# Thermocouple_datalogger_RevB.net
KiCad netlist of a schematic drawn in EAGLE
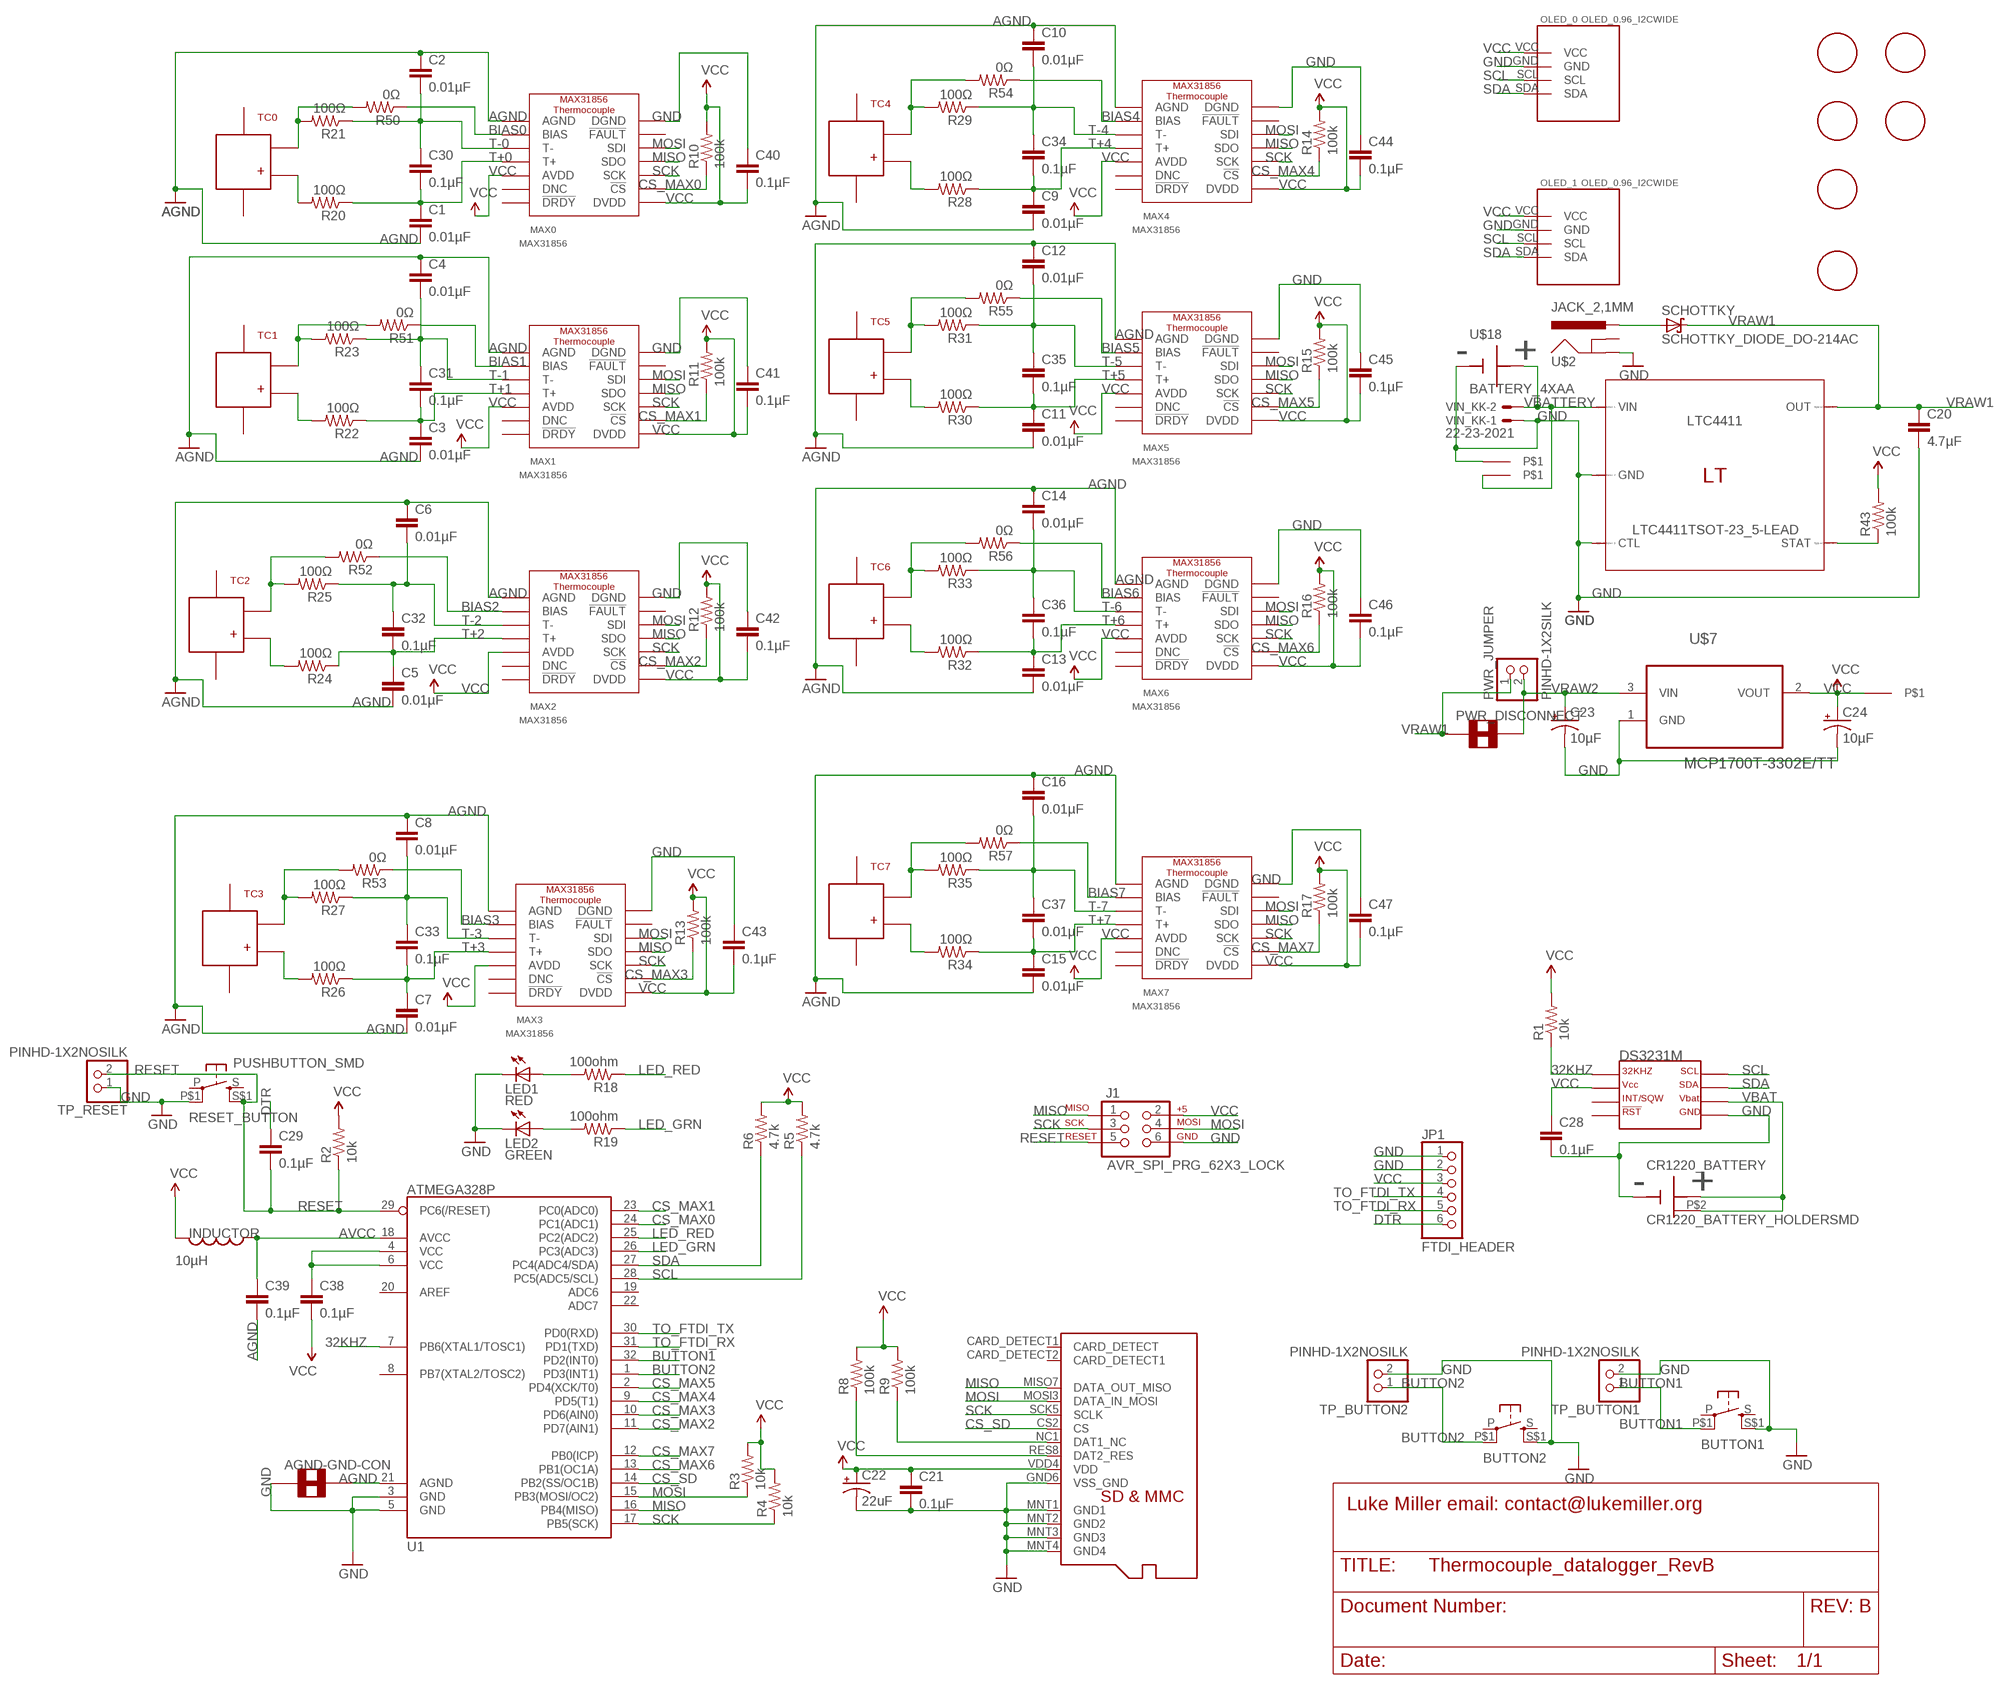
[diagram p0: schematic, sheet 1]

(export (version "E")
  (design (tool "Eeschema 10.0.6"))
  (components
    (comp (ref "AGND-GND-CON")
      (value "SOLDER_JUMPER_TRACESTANDARD")
      (footprint "eagle-import:SJ_2S-TRACE")
      (libsource (lib "eagle-import") (part "SOLDER_JUMPER_TRACESTANDARD"))
    )
    (comp (ref "BUTTON1")
      (value "PUSHBUTTON_DPST_SMDSTANDARD")
      (footprint "eagle-import:PUSHBUTTON_DPST_SMD")
      (libsource (lib "eagle-import") (part "PUSHBUTTON_DPST_SMDSTANDARD"))
    )
    (comp (ref "BUTTON2")
      (value "PUSHBUTTON_DPST_SMDSTANDARD")
      (footprint "eagle-import:PUSHBUTTON_DPST_SMD")
      (libsource (lib "eagle-import") (part "PUSHBUTTON_DPST_SMDSTANDARD"))
    )
    (comp (ref "C1")
      (value "0.01µF")
      (footprint "eagle-import:0805")
      (libsource (lib "eagle-import") (part "CAP0805"))
    )
    (comp (ref "C2")
      (value "0.01µF")
      (footprint "eagle-import:0805")
      (libsource (lib "eagle-import") (part "CAP0805"))
    )
    (comp (ref "C3")
      (value "0.01µF")
      (footprint "eagle-import:0805")
      (libsource (lib "eagle-import") (part "CAP0805"))
    )
    (comp (ref "C4")
      (value "0.01µF")
      (footprint "eagle-import:0805")
      (libsource (lib "eagle-import") (part "CAP0805"))
    )
    (comp (ref "C5")
      (value "0.01µF")
      (footprint "eagle-import:0805")
      (libsource (lib "eagle-import") (part "CAP0805"))
    )
    (comp (ref "C6")
      (value "0.01µF")
      (footprint "eagle-import:0805")
      (libsource (lib "eagle-import") (part "CAP0805"))
    )
    (comp (ref "C7")
      (value "0.01µF")
      (footprint "eagle-import:0805")
      (libsource (lib "eagle-import") (part "CAP0805"))
    )
    (comp (ref "C8")
      (value "0.01µF")
      (footprint "eagle-import:0805")
      (libsource (lib "eagle-import") (part "CAP0805"))
    )
    (comp (ref "C9")
      (value "0.01µF")
      (footprint "eagle-import:0805")
      (libsource (lib "eagle-import") (part "CAP0805"))
    )
    (comp (ref "C10")
      (value "0.01µF")
      (footprint "eagle-import:0805")
      (libsource (lib "eagle-import") (part "CAP0805"))
    )
    (comp (ref "C11")
      (value "0.01µF")
      (footprint "eagle-import:0805")
      (libsource (lib "eagle-import") (part "CAP0805"))
    )
    (comp (ref "C12")
      (value "0.01µF")
      (footprint "eagle-import:0805")
      (libsource (lib "eagle-import") (part "CAP0805"))
    )
    (comp (ref "C13")
      (value "0.01µF")
      (footprint "eagle-import:0805")
      (libsource (lib "eagle-import") (part "CAP0805"))
    )
    (comp (ref "C14")
      (value "0.01µF")
      (footprint "eagle-import:0805")
      (libsource (lib "eagle-import") (part "CAP0805"))
    )
    (comp (ref "C15")
      (value "0.01µF")
      (footprint "eagle-import:0805")
      (libsource (lib "eagle-import") (part "CAP0805"))
    )
    (comp (ref "C16")
      (value "0.01µF")
      (footprint "eagle-import:0805")
      (libsource (lib "eagle-import") (part "CAP0805"))
    )
    (comp (ref "C20")
      (value "4.7µF")
      (footprint "eagle-import:0805")
      (libsource (lib "eagle-import") (part "CAP0805"))
    )
    (comp (ref "C21")
      (value "0.1µF")
      (footprint "eagle-import:0805")
      (libsource (lib "eagle-import") (part "CAP0805"))
    )
    (comp (ref "C22")
      (value "22uF")
      (footprint "eagle-import:C0805_POL")
      (libsource (lib "eagle-import") (part "CPOL-US0805"))
    )
    (comp (ref "C23")
      (value "10µF")
      (footprint "eagle-import:PANASONIC_B")
      (libsource (lib "eagle-import") (part "CPOL-USB"))
    )
    (comp (ref "C24")
      (value "10µF")
      (footprint "eagle-import:PANASONIC_B")
      (libsource (lib "eagle-import") (part "CPOL-USB"))
    )
    (comp (ref "C28")
      (value "0.1µF")
      (footprint "eagle-import:0805")
      (libsource (lib "eagle-import") (part "CAP0805"))
    )
    (comp (ref "C29")
      (value "0.1µF")
      (footprint "eagle-import:0805")
      (libsource (lib "eagle-import") (part "CAP0805"))
    )
    (comp (ref "C30")
      (value "0.1µF")
      (footprint "eagle-import:0805")
      (libsource (lib "eagle-import") (part "CAP0805"))
    )
    (comp (ref "C31")
      (value "0.1µF")
      (footprint "eagle-import:0805")
      (libsource (lib "eagle-import") (part "CAP0805"))
    )
    (comp (ref "C32")
      (value "0.1µF")
      (footprint "eagle-import:0805")
      (libsource (lib "eagle-import") (part "CAP0805"))
    )
    (comp (ref "C33")
      (value "0.1µF")
      (footprint "eagle-import:0805")
      (libsource (lib "eagle-import") (part "CAP0805"))
    )
    (comp (ref "C34")
      (value "0.1µF")
      (footprint "eagle-import:0805")
      (libsource (lib "eagle-import") (part "CAP0805"))
    )
    (comp (ref "C35")
      (value "0.1µF")
      (footprint "eagle-import:0805")
      (libsource (lib "eagle-import") (part "CAP0805"))
    )
    (comp (ref "C36")
      (value "0.1µF")
      (footprint "eagle-import:0805")
      (libsource (lib "eagle-import") (part "CAP0805"))
    )
    (comp (ref "C37")
      (value "0.01µF")
      (footprint "eagle-import:0805")
      (libsource (lib "eagle-import") (part "CAP0805"))
    )
    (comp (ref "C38")
      (value "0.1µF")
      (footprint "eagle-import:0805")
      (libsource (lib "eagle-import") (part "CAP0805"))
    )
    (comp (ref "C39")
      (value "0.1µF")
      (footprint "eagle-import:0805")
      (libsource (lib "eagle-import") (part "CAP0805"))
    )
    (comp (ref "C40")
      (value "0.1µF")
      (footprint "eagle-import:0805")
      (libsource (lib "eagle-import") (part "CAP0805"))
    )
    (comp (ref "C41")
      (value "0.1µF")
      (footprint "eagle-import:0805")
      (libsource (lib "eagle-import") (part "CAP0805"))
    )
    (comp (ref "C42")
      (value "0.1µF")
      (footprint "eagle-import:0805")
      (libsource (lib "eagle-import") (part "CAP0805"))
    )
    (comp (ref "C43")
      (value "0.1µF")
      (footprint "eagle-import:0805")
      (libsource (lib "eagle-import") (part "CAP0805"))
    )
    (comp (ref "C44")
      (value "0.1µF")
      (footprint "eagle-import:0805")
      (libsource (lib "eagle-import") (part "CAP0805"))
    )
    (comp (ref "C45")
      (value "0.1µF")
      (footprint "eagle-import:0805")
      (libsource (lib "eagle-import") (part "CAP0805"))
    )
    (comp (ref "C46")
      (value "0.1µF")
      (footprint "eagle-import:0805")
      (libsource (lib "eagle-import") (part "CAP0805"))
    )
    (comp (ref "C47")
      (value "0.1µF")
      (footprint "eagle-import:0805")
      (libsource (lib "eagle-import") (part "CAP0805"))
    )
    (comp (ref "CR1220_BATTERY")
      (value "CR1220_BATTERY_HOLDERSMD")
      (footprint "eagle-import:CR1220_BATTERY_HOLDER_SMD")
      (libsource (lib "eagle-import") (part "CR1220_BATTERY_HOLDERSMD"))
    )
    (comp (ref "DS3231M")
      (value "DS3231MSOIC-8")
      (footprint "eagle-import:DS3231M_SOIC8")
      (libsource (lib "eagle-import") (part "DS3231MSOIC-8"))
    )
    (comp (ref "INDUCTOR")
      (value "10µH")
      (footprint "eagle-import:I_0805")
      (libsource (lib "eagle-import") (part "INDUCTOR0805_TY"))
    )
    (comp (ref "J1")
      (value "AVR_SPI_PRG_62X3_LOCK")
      (footprint "eagle-import:2X3_LOCK")
      (libsource (lib "eagle-import") (part "AVR_SPI_PRG_62X3_LOCK"))
    )
    (comp (ref "JP1")
      (value "FTDI_HEADER")
      (footprint "eagle-import:1X06-RIGHT_ANGLE")
      (libsource (lib "eagle-import") (part "PINHD-1X6RA"))
    )
    (comp (ref "LED1")
      (value "RED")
      (footprint "eagle-import:CHIPLED_0805")
      (libsource (lib "eagle-import") (part "LED0805"))
    )
    (comp (ref "LED2")
      (value "GREEN")
      (footprint "eagle-import:CHIPLED_0805")
      (libsource (lib "eagle-import") (part "LED0805"))
    )
    (comp (ref "LTC4411")
      (value "LTC4411TSOT-23_5-LEAD")
      (footprint "eagle-import:TSOT-23_5-LEAD")
      (libsource (lib "eagle-import") (part "LTC4411TSOT-23_5-LEAD"))
    )
    (comp (ref "MAX0")
      (value "MAX31856")
      (footprint "eagle-import:MAX31856_TSSOP14")
      (libsource (lib "eagle-import") (part "MAX31856"))
    )
    (comp (ref "MAX1")
      (value "MAX31856")
      (footprint "eagle-import:MAX31856_TSSOP14")
      (libsource (lib "eagle-import") (part "MAX31856"))
    )
    (comp (ref "MAX2")
      (value "MAX31856")
      (footprint "eagle-import:MAX31856_TSSOP14")
      (libsource (lib "eagle-import") (part "MAX31856"))
    )
    (comp (ref "MAX3")
      (value "MAX31856")
      (footprint "eagle-import:MAX31856_TSSOP14")
      (libsource (lib "eagle-import") (part "MAX31856"))
    )
    (comp (ref "MAX4")
      (value "MAX31856")
      (footprint "eagle-import:MAX31856_TSSOP14")
      (libsource (lib "eagle-import") (part "MAX31856"))
    )
    (comp (ref "MAX5")
      (value "MAX31856")
      (footprint "eagle-import:MAX31856_TSSOP14")
      (libsource (lib "eagle-import") (part "MAX31856"))
    )
    (comp (ref "MAX6")
      (value "MAX31856")
      (footprint "eagle-import:MAX31856_TSSOP14")
      (libsource (lib "eagle-import") (part "MAX31856"))
    )
    (comp (ref "MAX7")
      (value "MAX31856")
      (footprint "eagle-import:MAX31856_TSSOP14")
      (libsource (lib "eagle-import") (part "MAX31856"))
    )
    (comp (ref "OLED_0")
      (value "OLED_0.96_I2CWIDE")
      (footprint "eagle-import:OLED_0.96_I2C_VCC_PIN1_WIDE")
      (libsource (lib "eagle-import") (part "OLED_0.96_I2CWIDE"))
    )
    (comp (ref "OLED_1")
      (value "OLED_0.96_I2CWIDE")
      (footprint "eagle-import:OLED_0.96_I2C_VCC_PIN1_WIDE")
      (libsource (lib "eagle-import") (part "OLED_0.96_I2CWIDE"))
    )
    (comp (ref "PWR_DISCONNECT")
      (value "SOLDER_JUMPER_TRACESTANDARD")
      (footprint "eagle-import:SJ_2S-TRACE")
      (libsource (lib "eagle-import") (part "SOLDER_JUMPER_TRACESTANDARD"))
    )
    (comp (ref "PWR_JUMPER")
      (value "PINHD-1X2SILK")
      (footprint "eagle-import:1X02")
      (libsource (lib "eagle-import") (part "PINHD-1X2SILK"))
    )
    (comp (ref "R1")
      (value "10k")
      (footprint "eagle-import:R0805")
      (libsource (lib "eagle-import") (part "RESISTOR_SMDR0805"))
    )
    (comp (ref "R2")
      (value "10k")
      (footprint "eagle-import:R0805")
      (libsource (lib "eagle-import") (part "RESISTOR_SMDR0805"))
    )
    (comp (ref "R3")
      (value "10k")
      (footprint "eagle-import:R0805")
      (libsource (lib "eagle-import") (part "RESISTOR_SMDR0805"))
    )
    (comp (ref "R4")
      (value "10k")
      (footprint "eagle-import:R0805")
      (libsource (lib "eagle-import") (part "RESISTOR_SMDR0805"))
    )
    (comp (ref "R5")
      (value "4.7k")
      (footprint "eagle-import:R0805")
      (libsource (lib "eagle-import") (part "RESISTOR_SMDR0805"))
    )
    (comp (ref "R6")
      (value "4.7k")
      (footprint "eagle-import:R0805")
      (libsource (lib "eagle-import") (part "RESISTOR_SMDR0805"))
    )
    (comp (ref "R8")
      (value "100k")
      (footprint "eagle-import:R0805")
      (libsource (lib "eagle-import") (part "RESISTOR_SMDR0805"))
    )
    (comp (ref "R9")
      (value "100k")
      (footprint "eagle-import:R0805")
      (libsource (lib "eagle-import") (part "RESISTOR_SMDR0805"))
    )
    (comp (ref "R10")
      (value "100k")
      (footprint "eagle-import:R0805")
      (libsource (lib "eagle-import") (part "RESISTOR_SMDR0805"))
    )
    (comp (ref "R11")
      (value "100k")
      (footprint "eagle-import:R0805")
      (libsource (lib "eagle-import") (part "RESISTOR_SMDR0805"))
    )
    (comp (ref "R12")
      (value "100k")
      (footprint "eagle-import:R0805")
      (libsource (lib "eagle-import") (part "RESISTOR_SMDR0805"))
    )
    (comp (ref "R13")
      (value "100k")
      (footprint "eagle-import:R0805")
      (libsource (lib "eagle-import") (part "RESISTOR_SMDR0805"))
    )
    (comp (ref "R14")
      (value "100k")
      (footprint "eagle-import:R0805")
      (libsource (lib "eagle-import") (part "RESISTOR_SMDR0805"))
    )
    (comp (ref "R15")
      (value "100k")
      (footprint "eagle-import:R0805")
      (libsource (lib "eagle-import") (part "RESISTOR_SMDR0805"))
    )
    (comp (ref "R16")
      (value "100k")
      (footprint "eagle-import:R0805")
      (libsource (lib "eagle-import") (part "RESISTOR_SMDR0805"))
    )
    (comp (ref "R17")
      (value "100k")
      (footprint "eagle-import:R0805")
      (libsource (lib "eagle-import") (part "RESISTOR_SMDR0805"))
    )
    (comp (ref "R18")
      (value "100ohm")
      (footprint "eagle-import:R0805")
      (libsource (lib "eagle-import") (part "RESISTOR_SMDR0805"))
    )
    (comp (ref "R19")
      (value "100ohm")
      (footprint "eagle-import:R0805")
      (libsource (lib "eagle-import") (part "RESISTOR_SMDR0805"))
    )
    (comp (ref "R20")
      (value "100Ω")
      (footprint "eagle-import:R0805")
      (libsource (lib "eagle-import") (part "RESISTOR_SMDR0805"))
    )
    (comp (ref "R21")
      (value "100Ω")
      (footprint "eagle-import:R0805")
      (libsource (lib "eagle-import") (part "RESISTOR_SMDR0805"))
    )
    (comp (ref "R22")
      (value "100Ω")
      (footprint "eagle-import:R0805")
      (libsource (lib "eagle-import") (part "RESISTOR_SMDR0805"))
    )
    (comp (ref "R23")
      (value "100Ω")
      (footprint "eagle-import:R0805")
      (libsource (lib "eagle-import") (part "RESISTOR_SMDR0805"))
    )
    (comp (ref "R24")
      (value "100Ω")
      (footprint "eagle-import:R0805")
      (libsource (lib "eagle-import") (part "RESISTOR_SMDR0805"))
    )
    (comp (ref "R25")
      (value "100Ω")
      (footprint "eagle-import:R0805")
      (libsource (lib "eagle-import") (part "RESISTOR_SMDR0805"))
    )
    (comp (ref "R26")
      (value "100Ω")
      (footprint "eagle-import:R0805")
      (libsource (lib "eagle-import") (part "RESISTOR_SMDR0805"))
    )
    (comp (ref "R27")
      (value "100Ω")
      (footprint "eagle-import:R0805")
      (libsource (lib "eagle-import") (part "RESISTOR_SMDR0805"))
    )
    (comp (ref "R28")
      (value "100Ω")
      (footprint "eagle-import:R0805")
      (libsource (lib "eagle-import") (part "RESISTOR_SMDR0805"))
    )
    (comp (ref "R29")
      (value "100Ω")
      (footprint "eagle-import:R0805")
      (libsource (lib "eagle-import") (part "RESISTOR_SMDR0805"))
    )
    (comp (ref "R30")
      (value "100Ω")
      (footprint "eagle-import:R0805")
      (libsource (lib "eagle-import") (part "RESISTOR_SMDR0805"))
    )
    (comp (ref "R31")
      (value "100Ω")
      (footprint "eagle-import:R0805")
      (libsource (lib "eagle-import") (part "RESISTOR_SMDR0805"))
    )
    (comp (ref "R32")
      (value "100Ω")
      (footprint "eagle-import:R0805")
      (libsource (lib "eagle-import") (part "RESISTOR_SMDR0805"))
    )
    (comp (ref "R33")
      (value "100Ω")
      (footprint "eagle-import:R0805")
      (libsource (lib "eagle-import") (part "RESISTOR_SMDR0805"))
    )
    (comp (ref "R34")
      (value "100Ω")
      (footprint "eagle-import:R0805")
      (libsource (lib "eagle-import") (part "RESISTOR_SMDR0805"))
    )
    (comp (ref "R35")
      (value "100Ω")
      (footprint "eagle-import:R0805")
      (libsource (lib "eagle-import") (part "RESISTOR_SMDR0805"))
    )
    (comp (ref "R43")
      (value "100k")
      (footprint "eagle-import:R0805")
      (libsource (lib "eagle-import") (part "RESISTOR_SMDR0805"))
    )
    (comp (ref "R50")
      (value "0Ω")
      (footprint "eagle-import:R0805")
      (libsource (lib "eagle-import") (part "RESISTOR_SMDR0805"))
    )
    (comp (ref "R51")
      (value "0Ω")
      (footprint "eagle-import:R0805")
      (libsource (lib "eagle-import") (part "RESISTOR_SMDR0805"))
    )
    (comp (ref "R52")
      (value "0Ω")
      (footprint "eagle-import:R0805")
      (libsource (lib "eagle-import") (part "RESISTOR_SMDR0805"))
    )
    (comp (ref "R53")
      (value "0Ω")
      (footprint "eagle-import:R0805")
      (libsource (lib "eagle-import") (part "RESISTOR_SMDR0805"))
    )
    (comp (ref "R54")
      (value "0Ω")
      (footprint "eagle-import:R0805")
      (libsource (lib "eagle-import") (part "RESISTOR_SMDR0805"))
    )
    (comp (ref "R55")
      (value "0Ω")
      (footprint "eagle-import:R0805")
      (libsource (lib "eagle-import") (part "RESISTOR_SMDR0805"))
    )
    (comp (ref "R56")
      (value "0Ω")
      (footprint "eagle-import:R0805")
      (libsource (lib "eagle-import") (part "RESISTOR_SMDR0805"))
    )
    (comp (ref "R57")
      (value "0Ω")
      (footprint "eagle-import:R0805")
      (libsource (lib "eagle-import") (part "RESISTOR_SMDR0805"))
    )
    (comp (ref "RESET_BUTTON")
      (value "PUSHBUTTON_SMD")
      (footprint "eagle-import:PUSHBUTTON_DPST_SMD")
      (libsource (lib "eagle-import") (part "PUSHBUTTON_DPST_SMDSTANDARD"))
    )
    (comp (ref "SCHOTTKY")
      (value "SCHOTTKY_DIODE_DO-214AC")
      (footprint "eagle-import:DO214AC")
      (libsource (lib "eagle-import") (part "SCHOTTKY_DIODE_DO-214AC"))
    )
    (comp (ref "TC0")
      (value "PCC-SMP-THERMOCOUPLEVERTICAL")
      (footprint "eagle-import:PCC-SMP-V")
      (libsource (lib "eagle-import") (part "PCC-SMP-THERMOCOUPLEVERTICAL"))
    )
    (comp (ref "TC1")
      (value "PCC-SMP-THERMOCOUPLEVERTICAL")
      (footprint "eagle-import:PCC-SMP-V")
      (libsource (lib "eagle-import") (part "PCC-SMP-THERMOCOUPLEVERTICAL"))
    )
    (comp (ref "TC2")
      (value "PCC-SMP-THERMOCOUPLEVERTICAL")
      (footprint "eagle-import:PCC-SMP-V")
      (libsource (lib "eagle-import") (part "PCC-SMP-THERMOCOUPLEVERTICAL"))
    )
    (comp (ref "TC3")
      (value "PCC-SMP-THERMOCOUPLEVERTICAL")
      (footprint "eagle-import:PCC-SMP-V")
      (libsource (lib "eagle-import") (part "PCC-SMP-THERMOCOUPLEVERTICAL"))
    )
    (comp (ref "TC4")
      (value "PCC-SMP-THERMOCOUPLEVERTICAL")
      (footprint "eagle-import:PCC-SMP-V")
      (libsource (lib "eagle-import") (part "PCC-SMP-THERMOCOUPLEVERTICAL"))
    )
    (comp (ref "TC5")
      (value "PCC-SMP-THERMOCOUPLEVERTICAL")
      (footprint "eagle-import:PCC-SMP-V")
      (libsource (lib "eagle-import") (part "PCC-SMP-THERMOCOUPLEVERTICAL"))
    )
    (comp (ref "TC6")
      (value "PCC-SMP-THERMOCOUPLEVERTICAL")
      (footprint "eagle-import:PCC-SMP-V")
      (libsource (lib "eagle-import") (part "PCC-SMP-THERMOCOUPLEVERTICAL"))
    )
    (comp (ref "TC7")
      (value "PCC-SMP-THERMOCOUPLEVERTICAL")
      (footprint "eagle-import:PCC-SMP-V")
      (libsource (lib "eagle-import") (part "PCC-SMP-THERMOCOUPLEVERTICAL"))
    )
    (comp (ref "TP_BUTTON1")
      (value "PINHD-1X2NOSILK")
      (footprint "eagle-import:1X02_NOSILK")
      (libsource (lib "eagle-import") (part "PINHD-1X2NOSILK"))
    )
    (comp (ref "TP_BUTTON2")
      (value "PINHD-1X2NOSILK")
      (footprint "eagle-import:1X02_NOSILK")
      (libsource (lib "eagle-import") (part "PINHD-1X2NOSILK"))
    )
    (comp (ref "TP_GND")
      (value "PINHD-1X1STANDARD")
      (footprint "eagle-import:1X01")
      (libsource (lib "eagle-import") (part "PINHD-1X1STANDARD"))
    )
    (comp (ref "TP_RESET")
      (value "PINHD-1X2NOSILK")
      (footprint "eagle-import:1X02_NOSILK")
      (libsource (lib "eagle-import") (part "PINHD-1X2NOSILK"))
    )
    (comp (ref "TP_VBAT")
      (value "PINHD-1X1STANDARD")
      (footprint "eagle-import:1X01")
      (libsource (lib "eagle-import") (part "PINHD-1X1STANDARD"))
    )
    (comp (ref "U$2")
      (value "JACK_2,1MM")
      (footprint "eagle-import:POWER_JACK_DC_2,1MM")
      (libsource (lib "eagle-import") (part "POWER_JACK_2,1MM"))
    )
    (comp (ref "U$5")
      (value "MICROSD_MOLEX_REVERSECURRENT")
      (footprint "eagle-import:MICROSD_SOCKET_MOLEX_REVERSEMOUNT")
      (libsource (lib "eagle-import") (part "MICROSD_MOLEX_REVERSECURRENT"))
    )
    (comp (ref "U$6")
      (value "HOLE-LAYOUT4-40-SOCKET-HEAD")
      (footprint "eagle-import:4-40-SCREW-HOLE")
      (libsource (lib "eagle-import") (part "HOLE-LAYOUT4-40-SOCKET-HEAD"))
    )
    (comp (ref "U$7")
      (value "MCP1700T-3302E/TT")
      (footprint "eagle-import:SOT95P237X112-3N")
      (libsource (lib "eagle-import") (part "MCP1700T-3302E/TT"))
    )
    (comp (ref "U$15")
      (value "HOLE-LAYOUT4-40-SOCKET-HEAD")
      (footprint "eagle-import:4-40-SCREW-HOLE")
      (libsource (lib "eagle-import") (part "HOLE-LAYOUT4-40-SOCKET-HEAD"))
    )
    (comp (ref "U$16")
      (value "HOLE-LAYOUT4-40-SOCKET-HEAD")
      (footprint "eagle-import:4-40-SCREW-HOLE")
      (libsource (lib "eagle-import") (part "HOLE-LAYOUT4-40-SOCKET-HEAD"))
    )
    (comp (ref "U$18")
      (value "BATTERY_4XAA")
      (footprint "eagle-import:BATTERY_4XAA_PTH")
      (libsource (lib "eagle-import") (part "BATTERY_4XAA"))
    )
    (comp (ref "U$23")
      (value "HOLE-LAYOUT4-40-SOCKET-HEAD")
      (footprint "eagle-import:4-40-SCREW-HOLE")
      (libsource (lib "eagle-import") (part "HOLE-LAYOUT4-40-SOCKET-HEAD"))
    )
    (comp (ref "U$24")
      (value "HOLE-LAYOUT4-40-SOCKET-HEAD")
      (footprint "eagle-import:4-40-SCREW-HOLE")
      (libsource (lib "eagle-import") (part "HOLE-LAYOUT4-40-SOCKET-HEAD"))
    )
    (comp (ref "U$25")
      (value "HOLE-LAYOUT4-40-SOCKET-HEAD")
      (footprint "eagle-import:4-40-SCREW-HOLE")
      (libsource (lib "eagle-import") (part "HOLE-LAYOUT4-40-SOCKET-HEAD"))
    )
    (comp (ref "U1")
      (value "ATMEGA328P")
      (footprint "eagle-import:TQFP32-08")
      (libsource (lib "eagle-import") (part "ATMEGA328_SMT"))
    )
    (comp (ref "VCC")
      (value "PINHD-1X1STANDARD")
      (footprint "eagle-import:1X01")
      (libsource (lib "eagle-import") (part "PINHD-1X1STANDARD"))
    )
    (comp (ref "VIN_KK")
      (value "22-23-2021")
      (footprint "eagle-import:22-23-2021")
      (fields (field (name "MF") "MOLEX"))
      (libsource (lib "eagle-import") (part "22-23-2021"))
    )
  )
  (nets
    (net (code "1") (name "/32KHZ") (class "Default")
      (node (ref "DS3231M") (pin "1") (pinfunction "P$1_32KHZ_1") (pintype "bidirectional"))
      (node (ref "R1") (pin "1") (pinfunction "1_1") (pintype "passive"))
      (node (ref "U1") (pin "7") (pinfunction "PB6(XTAL1/TOSC1)_7") (pintype "bidirectional"))
    )
    (net (code "2") (name "/AVCC") (class "Default")
      (node (ref "C39") (pin "1") (pinfunction "1_1") (pintype "passive"))
      (node (ref "INDUCTOR") (pin "P$1") (pinfunction "1_P$1") (pintype "passive"))
      (node (ref "U1") (pin "18") (pinfunction "AVCC_18") (pintype "bidirectional"))
    )
    (net (code "3") (name "/BIAS0") (class "Default")
      (node (ref "MAX0") (pin "BIAS") (pinfunction "BIAS_BIAS") (pintype "bidirectional"))
      (node (ref "R50") (pin "1") (pinfunction "1_1") (pintype "passive"))
    )
    (net (code "4") (name "/BIAS1") (class "Default")
      (node (ref "MAX1") (pin "BIAS") (pinfunction "BIAS_BIAS") (pintype "bidirectional"))
      (node (ref "R51") (pin "1") (pinfunction "1_1") (pintype "passive"))
    )
    (net (code "5") (name "/BIAS2") (class "Default")
      (node (ref "MAX2") (pin "BIAS") (pinfunction "BIAS_BIAS") (pintype "bidirectional"))
      (node (ref "R52") (pin "1") (pinfunction "1_1") (pintype "passive"))
    )
    (net (code "6") (name "/BIAS3") (class "Default")
      (node (ref "MAX3") (pin "BIAS") (pinfunction "BIAS_BIAS") (pintype "bidirectional"))
      (node (ref "R53") (pin "1") (pinfunction "1_1") (pintype "passive"))
    )
    (net (code "7") (name "/BIAS4") (class "Default")
      (node (ref "MAX4") (pin "BIAS") (pinfunction "BIAS_BIAS") (pintype "bidirectional"))
      (node (ref "R54") (pin "1") (pinfunction "1_1") (pintype "passive"))
    )
    (net (code "8") (name "/BIAS5") (class "Default")
      (node (ref "MAX5") (pin "BIAS") (pinfunction "BIAS_BIAS") (pintype "bidirectional"))
      (node (ref "R55") (pin "1") (pinfunction "1_1") (pintype "passive"))
    )
    (net (code "9") (name "/BIAS6") (class "Default")
      (node (ref "MAX6") (pin "BIAS") (pinfunction "BIAS_BIAS") (pintype "bidirectional"))
      (node (ref "R56") (pin "1") (pinfunction "1_1") (pintype "passive"))
    )
    (net (code "10") (name "/BIAS7") (class "Default")
      (node (ref "MAX7") (pin "BIAS") (pinfunction "BIAS_BIAS") (pintype "bidirectional"))
      (node (ref "R57") (pin "1") (pinfunction "1_1") (pintype "passive"))
    )
    (net (code "11") (name "/BUTTON1") (class "Default")
      (node (ref "BUTTON1") (pin "P$1") (pinfunction "P1_P$1") (pintype "passive"))
      (node (ref "TP_BUTTON1") (pin "1") (pinfunction "1_1") (pintype "passive"))
      (node (ref "U1") (pin "32") (pinfunction "PD2(INT0)_32") (pintype "bidirectional"))
    )
    (net (code "12") (name "/BUTTON2") (class "Default")
      (node (ref "BUTTON2") (pin "P$1") (pinfunction "P1_P$1") (pintype "passive"))
      (node (ref "TP_BUTTON2") (pin "1") (pinfunction "1_1") (pintype "passive"))
      (node (ref "U1") (pin "1") (pinfunction "PD3(INT1)_1") (pintype "bidirectional"))
    )
    (net (code "13") (name "/CS_MAX0") (class "Default")
      (node (ref "MAX0") (pin "!CS") (pinfunction "~{CS}_!CS") (pintype "bidirectional"))
      (node (ref "R10") (pin "1") (pinfunction "1_1") (pintype "passive"))
      (node (ref "U1") (pin "24") (pinfunction "PC1(ADC1)_24") (pintype "bidirectional"))
    )
    (net (code "14") (name "/CS_MAX1") (class "Default")
      (node (ref "MAX1") (pin "!CS") (pinfunction "~{CS}_!CS") (pintype "bidirectional"))
      (node (ref "R11") (pin "1") (pinfunction "1_1") (pintype "passive"))
      (node (ref "U1") (pin "23") (pinfunction "PC0(ADC0)_23") (pintype "bidirectional"))
    )
    (net (code "15") (name "/CS_MAX2") (class "Default")
      (node (ref "MAX2") (pin "!CS") (pinfunction "~{CS}_!CS") (pintype "bidirectional"))
      (node (ref "R12") (pin "1") (pinfunction "1_1") (pintype "passive"))
      (node (ref "U1") (pin "11") (pinfunction "PD7(AIN1)_11") (pintype "bidirectional"))
    )
    (net (code "16") (name "/CS_MAX3") (class "Default")
      (node (ref "MAX3") (pin "!CS") (pinfunction "~{CS}_!CS") (pintype "bidirectional"))
      (node (ref "R13") (pin "1") (pinfunction "1_1") (pintype "passive"))
      (node (ref "U1") (pin "10") (pinfunction "PD6(AIN0)_10") (pintype "bidirectional"))
    )
    (net (code "17") (name "/CS_MAX4") (class "Default")
      (node (ref "MAX4") (pin "!CS") (pinfunction "~{CS}_!CS") (pintype "bidirectional"))
      (node (ref "R14") (pin "1") (pinfunction "1_1") (pintype "passive"))
      (node (ref "U1") (pin "9") (pinfunction "PD5(T1)_9") (pintype "bidirectional"))
    )
    (net (code "18") (name "/CS_MAX5") (class "Default")
      (node (ref "MAX5") (pin "!CS") (pinfunction "~{CS}_!CS") (pintype "bidirectional"))
      (node (ref "R15") (pin "1") (pinfunction "1_1") (pintype "passive"))
      (node (ref "U1") (pin "2") (pinfunction "PD4(XCK/T0)_2") (pintype "bidirectional"))
    )
    (net (code "19") (name "/CS_MAX6") (class "Default")
      (node (ref "MAX6") (pin "!CS") (pinfunction "~{CS}_!CS") (pintype "bidirectional"))
      (node (ref "R16") (pin "1") (pinfunction "1_1") (pintype "passive"))
      (node (ref "U1") (pin "13") (pinfunction "PB1(OC1A)_13") (pintype "bidirectional"))
    )
    (net (code "20") (name "/CS_MAX7") (class "Default")
      (node (ref "MAX7") (pin "!CS") (pinfunction "~{CS}_!CS") (pintype "bidirectional"))
      (node (ref "R17") (pin "1") (pinfunction "1_1") (pintype "passive"))
      (node (ref "U1") (pin "12") (pinfunction "PB0(ICP)_12") (pintype "bidirectional"))
    )
    (net (code "21") (name "/CS_SD") (class "Default")
      (node (ref "U$5") (pin "CS2") (pinfunction "CS_CS2") (pintype "input"))
      (node (ref "U1") (pin "14") (pinfunction "PB2(SS/OC1B)_14") (pintype "bidirectional"))
    )
    (net (code "22") (name "/DTR") (class "Default")
      (node (ref "C29") (pin "1") (pinfunction "1_1") (pintype "passive"))
      (node (ref "JP1") (pin "6") (pinfunction "6_6") (pintype "passive"))
    )
    (net (code "23") (name "/LED_GRN") (class "Default")
      (node (ref "R19") (pin "1") (pinfunction "1_1") (pintype "passive"))
      (node (ref "U1") (pin "26") (pinfunction "PC3(ADC3)_26") (pintype "bidirectional"))
    )
    (net (code "24") (name "/LED_RED") (class "Default")
      (node (ref "R18") (pin "1") (pinfunction "1_1") (pintype "passive"))
      (node (ref "U1") (pin "25") (pinfunction "PC2(ADC2)_25") (pintype "bidirectional"))
    )
    (net (code "25") (name "/MISO") (class "Default")
      (node (ref "J1") (pin "1") (pinfunction "1_1") (pintype "passive"))
      (node (ref "MAX0") (pin "SDO") (pinfunction "SDO_SDO") (pintype "bidirectional"))
      (node (ref "MAX1") (pin "SDO") (pinfunction "SDO_SDO") (pintype "bidirectional"))
      (node (ref "MAX2") (pin "SDO") (pinfunction "SDO_SDO") (pintype "bidirectional"))
      (node (ref "MAX3") (pin "SDO") (pinfunction "SDO_SDO") (pintype "bidirectional"))
      (node (ref "MAX4") (pin "SDO") (pinfunction "SDO_SDO") (pintype "bidirectional"))
      (node (ref "MAX5") (pin "SDO") (pinfunction "SDO_SDO") (pintype "bidirectional"))
      (node (ref "MAX6") (pin "SDO") (pinfunction "SDO_SDO") (pintype "bidirectional"))
      (node (ref "MAX7") (pin "SDO") (pinfunction "SDO_SDO") (pintype "bidirectional"))
      (node (ref "U$5") (pin "MISO7") (pinfunction "DATA_OUT_MISO_MISO7") (pintype "output"))
      (node (ref "U1") (pin "16") (pinfunction "PB4(MISO)_16") (pintype "bidirectional"))
    )
    (net (code "26") (name "/MOSI") (class "Default")
      (node (ref "J1") (pin "4") (pinfunction "4_4") (pintype "passive"))
      (node (ref "MAX0") (pin "SDI") (pinfunction "SDI_SDI") (pintype "bidirectional"))
      (node (ref "MAX1") (pin "SDI") (pinfunction "SDI_SDI") (pintype "bidirectional"))
      (node (ref "MAX2") (pin "SDI") (pinfunction "SDI_SDI") (pintype "bidirectional"))
      (node (ref "MAX3") (pin "SDI") (pinfunction "SDI_SDI") (pintype "bidirectional"))
      (node (ref "MAX4") (pin "SDI") (pinfunction "SDI_SDI") (pintype "bidirectional"))
      (node (ref "MAX5") (pin "SDI") (pinfunction "SDI_SDI") (pintype "bidirectional"))
      (node (ref "MAX6") (pin "SDI") (pinfunction "SDI_SDI") (pintype "bidirectional"))
      (node (ref "MAX7") (pin "SDI") (pinfunction "SDI_SDI") (pintype "bidirectional"))
      (node (ref "R3") (pin "1") (pinfunction "1_1") (pintype "passive"))
      (node (ref "U$5") (pin "MOSI3") (pinfunction "DATA_IN_MOSI_MOSI3") (pintype "input"))
      (node (ref "U1") (pin "15") (pinfunction "PB3(MOSI/OC2)_15") (pintype "bidirectional"))
    )
    (net (code "27") (name "/RESET") (class "Default")
      (node (ref "C29") (pin "2") (pinfunction "2_2") (pintype "passive"))
      (node (ref "J1") (pin "5") (pinfunction "5_5") (pintype "passive"))
      (node (ref "R2") (pin "1") (pinfunction "1_1") (pintype "passive"))
      (node (ref "RESET_BUTTON") (pin "S$1") (pinfunction "S1_S$1") (pintype "passive"))
      (node (ref "TP_RESET") (pin "2") (pinfunction "2_2") (pintype "passive"))
      (node (ref "U1") (pin "29") (pinfunction "PC6(/RESET)_29") (pintype "bidirectional"))
    )
    (net (code "28") (name "/SCK") (class "Default")
      (node (ref "J1") (pin "3") (pinfunction "3_3") (pintype "passive"))
      (node (ref "MAX0") (pin "SCK") (pinfunction "SCK_SCK") (pintype "bidirectional"))
      (node (ref "MAX1") (pin "SCK") (pinfunction "SCK_SCK") (pintype "bidirectional"))
      (node (ref "MAX2") (pin "SCK") (pinfunction "SCK_SCK") (pintype "bidirectional"))
      (node (ref "MAX3") (pin "SCK") (pinfunction "SCK_SCK") (pintype "bidirectional"))
      (node (ref "MAX4") (pin "SCK") (pinfunction "SCK_SCK") (pintype "bidirectional"))
      (node (ref "MAX5") (pin "SCK") (pinfunction "SCK_SCK") (pintype "bidirectional"))
      (node (ref "MAX6") (pin "SCK") (pinfunction "SCK_SCK") (pintype "bidirectional"))
      (node (ref "MAX7") (pin "SCK") (pinfunction "SCK_SCK") (pintype "bidirectional"))
      (node (ref "R4") (pin "1") (pinfunction "1_1") (pintype "passive"))
      (node (ref "U$5") (pin "SCK5") (pinfunction "SCLK_SCK5") (pintype "input"))
      (node (ref "U1") (pin "17") (pinfunction "PB5(SCK)_17") (pintype "bidirectional"))
    )
    (net (code "29") (name "/SCL") (class "Default")
      (node (ref "DS3231M") (pin "8") (pinfunction "P$8_SCL_8") (pintype "bidirectional"))
      (node (ref "OLED_0") (pin "SCL") (pinfunction "SCL_SCL") (pintype "bidirectional"))
      (node (ref "OLED_1") (pin "SCL") (pinfunction "SCL_SCL") (pintype "bidirectional"))
      (node (ref "R5") (pin "1") (pinfunction "1_1") (pintype "passive"))
      (node (ref "U1") (pin "28") (pinfunction "PC5(ADC5/SCL)_28") (pintype "bidirectional"))
    )
    (net (code "30") (name "/SDA") (class "Default")
      (node (ref "DS3231M") (pin "7") (pinfunction "P$7_SDA_7") (pintype "bidirectional"))
      (node (ref "OLED_0") (pin "SDA") (pinfunction "SDA_SDA") (pintype "bidirectional"))
      (node (ref "OLED_1") (pin "SDA") (pinfunction "SDA_SDA") (pintype "bidirectional"))
      (node (ref "R6") (pin "1") (pinfunction "1_1") (pintype "passive"))
      (node (ref "U1") (pin "27") (pinfunction "PC4(ADC4/SDA)_27") (pintype "bidirectional"))
    )
    (net (code "31") (name "/T+0") (class "Default")
      (node (ref "C1") (pin "1") (pinfunction "1_1") (pintype "passive"))
      (node (ref "C30") (pin "2") (pinfunction "2_2") (pintype "passive"))
      (node (ref "MAX0") (pin "T+") (pinfunction "T+_T+") (pintype "bidirectional"))
      (node (ref "R20") (pin "1") (pinfunction "1_1") (pintype "passive"))
    )
    (net (code "32") (name "/T+1") (class "Default")
      (node (ref "C3") (pin "1") (pinfunction "1_1") (pintype "passive"))
      (node (ref "C31") (pin "2") (pinfunction "2_2") (pintype "passive"))
      (node (ref "MAX1") (pin "T+") (pinfunction "T+_T+") (pintype "bidirectional"))
      (node (ref "R22") (pin "1") (pinfunction "1_1") (pintype "passive"))
    )
    (net (code "33") (name "/T+2") (class "Default")
      (node (ref "C32") (pin "2") (pinfunction "2_2") (pintype "passive"))
      (node (ref "C5") (pin "1") (pinfunction "1_1") (pintype "passive"))
      (node (ref "MAX2") (pin "T+") (pinfunction "T+_T+") (pintype "bidirectional"))
      (node (ref "R24") (pin "1") (pinfunction "1_1") (pintype "passive"))
    )
    (net (code "34") (name "/T+3") (class "Default")
      (node (ref "C33") (pin "2") (pinfunction "2_2") (pintype "passive"))
      (node (ref "C7") (pin "1") (pinfunction "1_1") (pintype "passive"))
      (node (ref "MAX3") (pin "T+") (pinfunction "T+_T+") (pintype "bidirectional"))
      (node (ref "R26") (pin "1") (pinfunction "1_1") (pintype "passive"))
    )
    (net (code "35") (name "/T+4") (class "Default")
      (node (ref "C34") (pin "2") (pinfunction "2_2") (pintype "passive"))
      (node (ref "C9") (pin "1") (pinfunction "1_1") (pintype "passive"))
      (node (ref "MAX4") (pin "T+") (pinfunction "T+_T+") (pintype "bidirectional"))
      (node (ref "R28") (pin "1") (pinfunction "1_1") (pintype "passive"))
    )
    (net (code "36") (name "/T+5") (class "Default")
      (node (ref "C11") (pin "1") (pinfunction "1_1") (pintype "passive"))
      (node (ref "C35") (pin "2") (pinfunction "2_2") (pintype "passive"))
      (node (ref "MAX5") (pin "T+") (pinfunction "T+_T+") (pintype "bidirectional"))
      (node (ref "R30") (pin "1") (pinfunction "1_1") (pintype "passive"))
    )
    (net (code "37") (name "/T+6") (class "Default")
      (node (ref "C13") (pin "1") (pinfunction "1_1") (pintype "passive"))
      (node (ref "C36") (pin "2") (pinfunction "2_2") (pintype "passive"))
      (node (ref "MAX6") (pin "T+") (pinfunction "T+_T+") (pintype "bidirectional"))
      (node (ref "R32") (pin "1") (pinfunction "1_1") (pintype "passive"))
    )
    (net (code "38") (name "/T+7") (class "Default")
      (node (ref "C15") (pin "1") (pinfunction "1_1") (pintype "passive"))
      (node (ref "C37") (pin "2") (pinfunction "2_2") (pintype "passive"))
      (node (ref "MAX7") (pin "T+") (pinfunction "T+_T+") (pintype "bidirectional"))
      (node (ref "R34") (pin "1") (pinfunction "1_1") (pintype "passive"))
    )
    (net (code "39") (name "/T-0") (class "Default")
      (node (ref "C2") (pin "2") (pinfunction "2_2") (pintype "passive"))
      (node (ref "C30") (pin "1") (pinfunction "1_1") (pintype "passive"))
      (node (ref "MAX0") (pin "T-") (pinfunction "T-_T-") (pintype "bidirectional"))
      (node (ref "R21") (pin "1") (pinfunction "1_1") (pintype "passive"))
    )
    (net (code "40") (name "/T-1") (class "Default")
      (node (ref "C31") (pin "1") (pinfunction "1_1") (pintype "passive"))
      (node (ref "C4") (pin "2") (pinfunction "2_2") (pintype "passive"))
      (node (ref "MAX1") (pin "T-") (pinfunction "T-_T-") (pintype "bidirectional"))
      (node (ref "R23") (pin "1") (pinfunction "1_1") (pintype "passive"))
    )
    (net (code "41") (name "/T-2") (class "Default")
      (node (ref "C32") (pin "1") (pinfunction "1_1") (pintype "passive"))
      (node (ref "C6") (pin "2") (pinfunction "2_2") (pintype "passive"))
      (node (ref "MAX2") (pin "T-") (pinfunction "T-_T-") (pintype "bidirectional"))
      (node (ref "R25") (pin "1") (pinfunction "1_1") (pintype "passive"))
    )
    (net (code "42") (name "/T-3") (class "Default")
      (node (ref "C33") (pin "1") (pinfunction "1_1") (pintype "passive"))
      (node (ref "C8") (pin "2") (pinfunction "2_2") (pintype "passive"))
      (node (ref "MAX3") (pin "T-") (pinfunction "T-_T-") (pintype "bidirectional"))
      (node (ref "R27") (pin "1") (pinfunction "1_1") (pintype "passive"))
    )
    (net (code "43") (name "/T-4") (class "Default")
      (node (ref "C10") (pin "2") (pinfunction "2_2") (pintype "passive"))
      (node (ref "C34") (pin "1") (pinfunction "1_1") (pintype "passive"))
      (node (ref "MAX4") (pin "T-") (pinfunction "T-_T-") (pintype "bidirectional"))
      (node (ref "R29") (pin "1") (pinfunction "1_1") (pintype "passive"))
    )
    (net (code "44") (name "/T-5") (class "Default")
      (node (ref "C12") (pin "2") (pinfunction "2_2") (pintype "passive"))
      (node (ref "C35") (pin "1") (pinfunction "1_1") (pintype "passive"))
      (node (ref "MAX5") (pin "T-") (pinfunction "T-_T-") (pintype "bidirectional"))
      (node (ref "R31") (pin "1") (pinfunction "1_1") (pintype "passive"))
    )
    (net (code "45") (name "/T-6") (class "Default")
      (node (ref "C14") (pin "2") (pinfunction "2_2") (pintype "passive"))
      (node (ref "C36") (pin "1") (pinfunction "1_1") (pintype "passive"))
      (node (ref "MAX6") (pin "T-") (pinfunction "T-_T-") (pintype "bidirectional"))
      (node (ref "R33") (pin "1") (pinfunction "1_1") (pintype "passive"))
    )
    (net (code "46") (name "/T-7") (class "Default")
      (node (ref "C16") (pin "2") (pinfunction "2_2") (pintype "passive"))
      (node (ref "C37") (pin "1") (pinfunction "1_1") (pintype "passive"))
      (node (ref "MAX7") (pin "T-") (pinfunction "T-_T-") (pintype "bidirectional"))
      (node (ref "R35") (pin "1") (pinfunction "1_1") (pintype "passive"))
    )
    (net (code "47") (name "/TO_FTDI_RX") (class "Default")
      (node (ref "JP1") (pin "5") (pinfunction "5_5") (pintype "passive"))
      (node (ref "U1") (pin "31") (pinfunction "PD1(TXD)_31") (pintype "bidirectional"))
    )
    (net (code "48") (name "/TO_FTDI_TX") (class "Default")
      (node (ref "JP1") (pin "4") (pinfunction "4_4") (pintype "passive"))
      (node (ref "U1") (pin "30") (pinfunction "PD0(RXD)_30") (pintype "bidirectional"))
    )
    (net (code "49") (name "/VBAT") (class "Default")
      (node (ref "CR1220_BATTERY") (pin "P$1") (pinfunction "VBAT_P$1") (pintype "power_in"))
      (node (ref "CR1220_BATTERY") (pin "P$2") (pinfunction "P$2_P$2") (pintype "power_in"))
      (node (ref "DS3231M") (pin "6") (pinfunction "P$6_VBAT_6") (pintype "bidirectional"))
    )
    (net (code "50") (name "/VBATTERY") (class "Default")
      (node (ref "LTC4411") (pin "1") (pinfunction "VIN_1") (pintype "passive"))
      (node (ref "TP_VBAT") (pin "1") (pinfunction "P$1_1") (pintype "bidirectional"))
      (node (ref "U$18") (pin "VBAT") (pinfunction "VBAT_VBAT") (pintype "power_in"))
      (node (ref "VIN_KK") (pin "2") (pinfunction "S_2") (pintype "passive"))
    )
    (net (code "51") (name "/VRAW1") (class "Default")
      (node (ref "C20") (pin "1") (pinfunction "1_1") (pintype "passive"))
      (node (ref "LTC4411") (pin "5") (pinfunction "OUT_5") (pintype "passive"))
      (node (ref "PWR_DISCONNECT") (pin "1") (pinfunction "P$1_1") (pintype "bidirectional"))
      (node (ref "PWR_JUMPER") (pin "1") (pinfunction "1_1") (pintype "passive"))
      (node (ref "SCHOTTKY") (pin "C") (pinfunction "C_C") (pintype "passive"))
    )
    (net (code "52") (name "/VRAW2") (class "Default")
      (node (ref "C23") (pin "+") (pinfunction "+_+") (pintype "passive"))
      (node (ref "PWR_DISCONNECT") (pin "2") (pinfunction "P$2_2") (pintype "bidirectional"))
      (node (ref "PWR_JUMPER") (pin "2") (pinfunction "2_2") (pintype "passive"))
      (node (ref "U$7") (pin "3") (pinfunction "VIN_3") (pintype "input"))
    )
    (net (code "53") (name "AGND") (class "Default")
      (node (ref "AGND-GND-CON") (pin "2") (pinfunction "P$2_2") (pintype "bidirectional"))
      (node (ref "C1") (pin "2") (pinfunction "2_2") (pintype "passive"))
      (node (ref "C10") (pin "1") (pinfunction "1_1") (pintype "passive"))
      (node (ref "C11") (pin "2") (pinfunction "2_2") (pintype "passive"))
      (node (ref "C12") (pin "1") (pinfunction "1_1") (pintype "passive"))
      (node (ref "C13") (pin "2") (pinfunction "2_2") (pintype "passive"))
      (node (ref "C14") (pin "1") (pinfunction "1_1") (pintype "passive"))
      (node (ref "C15") (pin "2") (pinfunction "2_2") (pintype "passive"))
      (node (ref "C16") (pin "1") (pinfunction "1_1") (pintype "passive"))
      (node (ref "C2") (pin "1") (pinfunction "1_1") (pintype "passive"))
      (node (ref "C3") (pin "2") (pinfunction "2_2") (pintype "passive"))
      (node (ref "C39") (pin "2") (pinfunction "2_2") (pintype "passive"))
      (node (ref "C4") (pin "1") (pinfunction "1_1") (pintype "passive"))
      (node (ref "C5") (pin "2") (pinfunction "2_2") (pintype "passive"))
      (node (ref "C6") (pin "1") (pinfunction "1_1") (pintype "passive"))
      (node (ref "C7") (pin "2") (pinfunction "2_2") (pintype "passive"))
      (node (ref "C8") (pin "1") (pinfunction "1_1") (pintype "passive"))
      (node (ref "C9") (pin "2") (pinfunction "2_2") (pintype "passive"))
      (node (ref "MAX0") (pin "AGND") (pinfunction "AGND_AGND") (pintype "bidirectional"))
      (node (ref "MAX1") (pin "AGND") (pinfunction "AGND_AGND") (pintype "bidirectional"))
      (node (ref "MAX2") (pin "AGND") (pinfunction "AGND_AGND") (pintype "bidirectional"))
      (node (ref "MAX3") (pin "AGND") (pinfunction "AGND_AGND") (pintype "bidirectional"))
      (node (ref "MAX4") (pin "AGND") (pinfunction "AGND_AGND") (pintype "bidirectional"))
      (node (ref "MAX5") (pin "AGND") (pinfunction "AGND_AGND") (pintype "bidirectional"))
      (node (ref "MAX6") (pin "AGND") (pinfunction "AGND_AGND") (pintype "bidirectional"))
      (node (ref "MAX7") (pin "AGND") (pinfunction "AGND_AGND") (pintype "bidirectional"))
      (node (ref "U1") (pin "21") (pinfunction "AGND_21") (pintype "bidirectional"))
    )
    (net (code "54") (name "GND") (class "Default")
      (node (ref "AGND-GND-CON") (pin "1") (pinfunction "P$1_1") (pintype "bidirectional"))
      (node (ref "BUTTON1") (pin "S$1") (pinfunction "S1_S$1") (pintype "passive"))
      (node (ref "BUTTON2") (pin "S$1") (pinfunction "S1_S$1") (pintype "passive"))
      (node (ref "C20") (pin "2") (pinfunction "2_2") (pintype "passive"))
      (node (ref "C21") (pin "2") (pinfunction "2_2") (pintype "passive"))
      (node (ref "C22") (pin "P$2_C") (pinfunction "-_P$2_C") (pintype "passive"))
      (node (ref "C23") (pin "-") (pinfunction "-_-") (pintype "passive"))
      (node (ref "C24") (pin "-") (pinfunction "-_-") (pintype "passive"))
      (node (ref "C28") (pin "2") (pinfunction "2_2") (pintype "passive"))
      (node (ref "C40") (pin "1") (pinfunction "1_1") (pintype "passive"))
      (node (ref "C41") (pin "1") (pinfunction "1_1") (pintype "passive"))
      (node (ref "C42") (pin "1") (pinfunction "1_1") (pintype "passive"))
      (node (ref "C43") (pin "1") (pinfunction "1_1") (pintype "passive"))
      (node (ref "C44") (pin "1") (pinfunction "1_1") (pintype "passive"))
      (node (ref "C45") (pin "1") (pinfunction "1_1") (pintype "passive"))
      (node (ref "C46") (pin "1") (pinfunction "1_1") (pintype "passive"))
      (node (ref "C47") (pin "1") (pinfunction "1_1") (pintype "passive"))
      (node (ref "CR1220_BATTERY") (pin "GND") (pinfunction "GND_GND") (pintype "power_in"))
      (node (ref "DS3231M") (pin "5") (pinfunction "P$5_GND_5") (pintype "power_in"))
      (node (ref "J1") (pin "6") (pinfunction "6_6") (pintype "passive"))
      (node (ref "JP1") (pin "1") (pinfunction "1_1") (pintype "passive"))
      (node (ref "JP1") (pin "2") (pinfunction "2_2") (pintype "passive"))
      (node (ref "LED1") (pin "C") (pinfunction "C_C") (pintype "passive"))
      (node (ref "LED2") (pin "C") (pinfunction "C_C") (pintype "passive"))
      (node (ref "LTC4411") (pin "2") (pinfunction "GND_2") (pintype "passive"))
      (node (ref "LTC4411") (pin "3") (pinfunction "CTL_3") (pintype "passive"))
      (node (ref "MAX0") (pin "DGND") (pinfunction "DGND_DGND") (pintype "bidirectional"))
      (node (ref "MAX1") (pin "DGND") (pinfunction "DGND_DGND") (pintype "bidirectional"))
      (node (ref "MAX2") (pin "DGND") (pinfunction "DGND_DGND") (pintype "bidirectional"))
      (node (ref "MAX3") (pin "DGND") (pinfunction "DGND_DGND") (pintype "bidirectional"))
      (node (ref "MAX4") (pin "DGND") (pinfunction "DGND_DGND") (pintype "bidirectional"))
      (node (ref "MAX5") (pin "DGND") (pinfunction "DGND_DGND") (pintype "bidirectional"))
      (node (ref "MAX6") (pin "DGND") (pinfunction "DGND_DGND") (pintype "bidirectional"))
      (node (ref "MAX7") (pin "DGND") (pinfunction "DGND_DGND") (pintype "bidirectional"))
      (node (ref "OLED_0") (pin "GND") (pinfunction "GND_GND") (pintype "bidirectional"))
      (node (ref "OLED_1") (pin "GND") (pinfunction "GND_GND") (pintype "bidirectional"))
      (node (ref "RESET_BUTTON") (pin "P$1") (pinfunction "P1_P$1") (pintype "passive"))
      (node (ref "TP_BUTTON1") (pin "2") (pinfunction "2_2") (pintype "passive"))
      (node (ref "TP_BUTTON2") (pin "2") (pinfunction "2_2") (pintype "passive"))
      (node (ref "TP_GND") (pin "1") (pinfunction "P$1_1") (pintype "bidirectional"))
      (node (ref "TP_RESET") (pin "1") (pinfunction "1_1") (pintype "passive"))
      (node (ref "U$18") (pin "GND") (pinfunction "GND_GND") (pintype "power_in"))
      (node (ref "U$2") (pin "P$2") (pinfunction "GND_P$2") (pintype "bidirectional"))
      (node (ref "U$5") (pin "GND6") (pinfunction "VSS_GND_GND6") (pintype "power_in"))
      (node (ref "U$5") (pin "MNT1") (pinfunction "GND1_MNT1") (pintype "power_in"))
      (node (ref "U$5") (pin "MNT2") (pinfunction "GND2_MNT2") (pintype "power_in"))
      (node (ref "U$5") (pin "MNT3") (pinfunction "GND3_MNT3") (pintype "power_in"))
      (node (ref "U$5") (pin "MNT4") (pinfunction "GND4_MNT4") (pintype "power_in"))
      (node (ref "U$7") (pin "1") (pinfunction "GND_1") (pintype "passive"))
      (node (ref "U1") (pin "3") (pinfunction "GND_3") (pintype "bidirectional"))
      (node (ref "U1") (pin "5") (pinfunction "GND_5") (pintype "bidirectional"))
      (node (ref "VIN_KK") (pin "1") (pinfunction "S_1") (pintype "passive"))
    )
    (net (code "55") (name "Net-(C38-Pad1)") (class "Default")
      (node (ref "C38") (pin "1") (pinfunction "1_1") (pintype "passive"))
      (node (ref "U1") (pin "4") (pinfunction "VCC_4") (pintype "bidirectional"))
      (node (ref "U1") (pin "6") (pinfunction "VCC_6") (pintype "bidirectional"))
    )
    (net (code "56") (name "Net-(LED1-PadA)") (class "Default")
      (node (ref "LED1") (pin "A") (pinfunction "A_A") (pintype "passive"))
      (node (ref "R18") (pin "2") (pinfunction "2_2") (pintype "passive"))
    )
    (net (code "57") (name "Net-(LED2-PadA)") (class "Default")
      (node (ref "LED2") (pin "A") (pinfunction "A_A") (pintype "passive"))
      (node (ref "R19") (pin "2") (pinfunction "2_2") (pintype "passive"))
    )
    (net (code "58") (name "Net-(LTC4411-STAT)") (class "Default")
      (node (ref "LTC4411") (pin "4") (pinfunction "STAT_4") (pintype "passive"))
      (node (ref "R43") (pin "1") (pinfunction "1_1") (pintype "passive"))
    )
    (net (code "59") (name "Net-(R20-Pad2)") (class "Default")
      (node (ref "R20") (pin "2") (pinfunction "2_2") (pintype "passive"))
      (node (ref "TC0") (pin "P$2") (pinfunction "P$2_P$2") (pintype "bidirectional"))
    )
    (net (code "60") (name "Net-(R21-Pad2)") (class "Default")
      (node (ref "R21") (pin "2") (pinfunction "2_2") (pintype "passive"))
      (node (ref "R50") (pin "2") (pinfunction "2_2") (pintype "passive"))
      (node (ref "TC0") (pin "P$1") (pinfunction "P$1_P$1") (pintype "bidirectional"))
    )
    (net (code "61") (name "Net-(R22-Pad2)") (class "Default")
      (node (ref "R22") (pin "2") (pinfunction "2_2") (pintype "passive"))
      (node (ref "TC1") (pin "P$2") (pinfunction "P$2_P$2") (pintype "bidirectional"))
    )
    (net (code "62") (name "Net-(R23-Pad2)") (class "Default")
      (node (ref "R23") (pin "2") (pinfunction "2_2") (pintype "passive"))
      (node (ref "R51") (pin "2") (pinfunction "2_2") (pintype "passive"))
      (node (ref "TC1") (pin "P$1") (pinfunction "P$1_P$1") (pintype "bidirectional"))
    )
    (net (code "63") (name "Net-(R24-Pad2)") (class "Default")
      (node (ref "R24") (pin "2") (pinfunction "2_2") (pintype "passive"))
      (node (ref "TC2") (pin "P$2") (pinfunction "P$2_P$2") (pintype "bidirectional"))
    )
    (net (code "64") (name "Net-(R25-Pad2)") (class "Default")
      (node (ref "R25") (pin "2") (pinfunction "2_2") (pintype "passive"))
      (node (ref "R52") (pin "2") (pinfunction "2_2") (pintype "passive"))
      (node (ref "TC2") (pin "P$1") (pinfunction "P$1_P$1") (pintype "bidirectional"))
    )
    (net (code "65") (name "Net-(R26-Pad2)") (class "Default")
      (node (ref "R26") (pin "2") (pinfunction "2_2") (pintype "passive"))
      (node (ref "TC3") (pin "P$2") (pinfunction "P$2_P$2") (pintype "bidirectional"))
    )
    (net (code "66") (name "Net-(R27-Pad2)") (class "Default")
      (node (ref "R27") (pin "2") (pinfunction "2_2") (pintype "passive"))
      (node (ref "R53") (pin "2") (pinfunction "2_2") (pintype "passive"))
      (node (ref "TC3") (pin "P$1") (pinfunction "P$1_P$1") (pintype "bidirectional"))
    )
    (net (code "67") (name "Net-(R28-Pad2)") (class "Default")
      (node (ref "R28") (pin "2") (pinfunction "2_2") (pintype "passive"))
      (node (ref "TC4") (pin "P$2") (pinfunction "P$2_P$2") (pintype "bidirectional"))
    )
    (net (code "68") (name "Net-(R29-Pad2)") (class "Default")
      (node (ref "R29") (pin "2") (pinfunction "2_2") (pintype "passive"))
      (node (ref "R54") (pin "2") (pinfunction "2_2") (pintype "passive"))
      (node (ref "TC4") (pin "P$1") (pinfunction "P$1_P$1") (pintype "bidirectional"))
    )
    (net (code "69") (name "Net-(R30-Pad2)") (class "Default")
      (node (ref "R30") (pin "2") (pinfunction "2_2") (pintype "passive"))
      (node (ref "TC5") (pin "P$2") (pinfunction "P$2_P$2") (pintype "bidirectional"))
    )
    (net (code "70") (name "Net-(R31-Pad2)") (class "Default")
      (node (ref "R31") (pin "2") (pinfunction "2_2") (pintype "passive"))
      (node (ref "R55") (pin "2") (pinfunction "2_2") (pintype "passive"))
      (node (ref "TC5") (pin "P$1") (pinfunction "P$1_P$1") (pintype "bidirectional"))
    )
    (net (code "71") (name "Net-(R32-Pad2)") (class "Default")
      (node (ref "R32") (pin "2") (pinfunction "2_2") (pintype "passive"))
      (node (ref "TC6") (pin "P$2") (pinfunction "P$2_P$2") (pintype "bidirectional"))
    )
    (net (code "72") (name "Net-(R33-Pad2)") (class "Default")
      (node (ref "R33") (pin "2") (pinfunction "2_2") (pintype "passive"))
      (node (ref "R56") (pin "2") (pinfunction "2_2") (pintype "passive"))
      (node (ref "TC6") (pin "P$1") (pinfunction "P$1_P$1") (pintype "bidirectional"))
    )
    (net (code "73") (name "Net-(R34-Pad2)") (class "Default")
      (node (ref "R34") (pin "2") (pinfunction "2_2") (pintype "passive"))
      (node (ref "TC7") (pin "P$2") (pinfunction "P$2_P$2") (pintype "bidirectional"))
    )
    (net (code "74") (name "Net-(R35-Pad2)") (class "Default")
      (node (ref "R35") (pin "2") (pinfunction "2_2") (pintype "passive"))
      (node (ref "R57") (pin "2") (pinfunction "2_2") (pintype "passive"))
      (node (ref "TC7") (pin "P$1") (pinfunction "P$1_P$1") (pintype "bidirectional"))
    )
    (net (code "75") (name "Net-(U$2-PWR)") (class "Default")
      (node (ref "SCHOTTKY") (pin "A") (pinfunction "A_A") (pintype "passive"))
      (node (ref "U$2") (pin "P$1") (pinfunction "PWR_P$1") (pintype "bidirectional"))
    )
    (net (code "76") (name "Net-(U$5-DAT1_NC)") (class "Default")
      (node (ref "R9") (pin "1") (pinfunction "1_1") (pintype "passive"))
      (node (ref "U$5") (pin "NC1") (pinfunction "DAT1_NC_NC1") (pintype "bidirectional"))
    )
    (net (code "77") (name "Net-(U$5-DAT2_RES)") (class "Default")
      (node (ref "R8") (pin "1") (pinfunction "1_1") (pintype "passive"))
      (node (ref "U$5") (pin "RES8") (pinfunction "DAT2_RES_RES8") (pintype "bidirectional"))
    )
    (net (code "78") (name "VCC") (class "Default")
      (node (ref "C21") (pin "1") (pinfunction "1_1") (pintype "passive"))
      (node (ref "C22") (pin "P$1_A") (pinfunction "+_P$1_A") (pintype "passive"))
      (node (ref "C24") (pin "+") (pinfunction "+_+") (pintype "passive"))
      (node (ref "C28") (pin "1") (pinfunction "1_1") (pintype "passive"))
      (node (ref "C38") (pin "2") (pinfunction "2_2") (pintype "passive"))
      (node (ref "C40") (pin "2") (pinfunction "2_2") (pintype "passive"))
      (node (ref "C41") (pin "2") (pinfunction "2_2") (pintype "passive"))
      (node (ref "C42") (pin "2") (pinfunction "2_2") (pintype "passive"))
      (node (ref "C43") (pin "2") (pinfunction "2_2") (pintype "passive"))
      (node (ref "C44") (pin "2") (pinfunction "2_2") (pintype "passive"))
      (node (ref "C45") (pin "2") (pinfunction "2_2") (pintype "passive"))
      (node (ref "C46") (pin "2") (pinfunction "2_2") (pintype "passive"))
      (node (ref "C47") (pin "2") (pinfunction "2_2") (pintype "passive"))
      (node (ref "DS3231M") (pin "2") (pinfunction "P$2_VCC_2") (pintype "power_in"))
      (node (ref "INDUCTOR") (pin "P$2") (pinfunction "2_P$2") (pintype "passive"))
      (node (ref "J1") (pin "2") (pinfunction "2_2") (pintype "passive"))
      (node (ref "JP1") (pin "3") (pinfunction "3_3") (pintype "passive"))
      (node (ref "MAX0") (pin "AVDD") (pinfunction "AVDD_AVDD") (pintype "power_in"))
      (node (ref "MAX0") (pin "DVDD") (pinfunction "DVDD_DVDD") (pintype "power_in"))
      (node (ref "MAX1") (pin "AVDD") (pinfunction "AVDD_AVDD") (pintype "power_in"))
      (node (ref "MAX1") (pin "DVDD") (pinfunction "DVDD_DVDD") (pintype "power_in"))
      (node (ref "MAX2") (pin "AVDD") (pinfunction "AVDD_AVDD") (pintype "power_in"))
      (node (ref "MAX2") (pin "DVDD") (pinfunction "DVDD_DVDD") (pintype "power_in"))
      (node (ref "MAX3") (pin "AVDD") (pinfunction "AVDD_AVDD") (pintype "power_in"))
      (node (ref "MAX3") (pin "DVDD") (pinfunction "DVDD_DVDD") (pintype "power_in"))
      (node (ref "MAX4") (pin "AVDD") (pinfunction "AVDD_AVDD") (pintype "power_in"))
      (node (ref "MAX4") (pin "DVDD") (pinfunction "DVDD_DVDD") (pintype "power_in"))
      (node (ref "MAX5") (pin "AVDD") (pinfunction "AVDD_AVDD") (pintype "power_in"))
      (node (ref "MAX5") (pin "DVDD") (pinfunction "DVDD_DVDD") (pintype "power_in"))
      (node (ref "MAX6") (pin "AVDD") (pinfunction "AVDD_AVDD") (pintype "power_in"))
      (node (ref "MAX6") (pin "DVDD") (pinfunction "DVDD_DVDD") (pintype "power_in"))
      (node (ref "MAX7") (pin "AVDD") (pinfunction "AVDD_AVDD") (pintype "power_in"))
      (node (ref "MAX7") (pin "DVDD") (pinfunction "DVDD_DVDD") (pintype "power_in"))
      (node (ref "OLED_0") (pin "VCC") (pinfunction "VCC_VCC") (pintype "bidirectional"))
      (node (ref "OLED_1") (pin "VCC") (pinfunction "VCC_VCC") (pintype "bidirectional"))
      (node (ref "R1") (pin "2") (pinfunction "2_2") (pintype "passive"))
      (node (ref "R10") (pin "2") (pinfunction "2_2") (pintype "passive"))
      (node (ref "R11") (pin "2") (pinfunction "2_2") (pintype "passive"))
      (node (ref "R12") (pin "2") (pinfunction "2_2") (pintype "passive"))
      (node (ref "R13") (pin "2") (pinfunction "2_2") (pintype "passive"))
      (node (ref "R14") (pin "2") (pinfunction "2_2") (pintype "passive"))
      (node (ref "R15") (pin "2") (pinfunction "2_2") (pintype "passive"))
      (node (ref "R16") (pin "2") (pinfunction "2_2") (pintype "passive"))
      (node (ref "R17") (pin "2") (pinfunction "2_2") (pintype "passive"))
      (node (ref "R2") (pin "2") (pinfunction "2_2") (pintype "passive"))
      (node (ref "R3") (pin "2") (pinfunction "2_2") (pintype "passive"))
      (node (ref "R4") (pin "2") (pinfunction "2_2") (pintype "passive"))
      (node (ref "R43") (pin "2") (pinfunction "2_2") (pintype "passive"))
      (node (ref "R5") (pin "2") (pinfunction "2_2") (pintype "passive"))
      (node (ref "R6") (pin "2") (pinfunction "2_2") (pintype "passive"))
      (node (ref "R8") (pin "2") (pinfunction "2_2") (pintype "passive"))
      (node (ref "R9") (pin "2") (pinfunction "2_2") (pintype "passive"))
      (node (ref "U$5") (pin "VDD4") (pinfunction "VDD_VDD4") (pintype "power_in"))
      (node (ref "U$7") (pin "2") (pinfunction "VOUT_2") (pintype "output"))
      (node (ref "VCC") (pin "1") (pinfunction "P$1_1") (pintype "bidirectional"))
    )
    (net (code "79") (name "unconnected-(BUTTON1-PadP)") (class "Default")
      (node (ref "BUTTON1") (pin "P") (pinfunction "P_P") (pintype "passive"))
    )
    (net (code "80") (name "unconnected-(BUTTON1-PadS)") (class "Default")
      (node (ref "BUTTON1") (pin "S") (pinfunction "S_S") (pintype "passive"))
    )
    (net (code "81") (name "unconnected-(BUTTON2-PadP)") (class "Default")
      (node (ref "BUTTON2") (pin "P") (pinfunction "P_P") (pintype "passive"))
    )
    (net (code "82") (name "unconnected-(BUTTON2-PadS)") (class "Default")
      (node (ref "BUTTON2") (pin "S") (pinfunction "S_S") (pintype "passive"))
    )
    (net (code "83") (name "unconnected-(DS3231M-P$3_INT-Pad3)") (class "Default")
      (node (ref "DS3231M") (pin "3") (pinfunction "P$3_INT_3") (pintype "bidirectional"))
    )
    (net (code "84") (name "unconnected-(DS3231M-P$4_RST-Pad4)") (class "Default")
      (node (ref "DS3231M") (pin "4") (pinfunction "P$4_RST_4") (pintype "bidirectional"))
    )
    (net (code "85") (name "unconnected-(MAX0-DNC-Pad6)") (class "Default")
      (node (ref "MAX0") (pin "6") (pinfunction "DNC_6") (pintype "no_connect"))
    )
    (net (code "86") (name "unconnected-(MAX0-~{DRDY}-Pad!DRDY)") (class "Default")
      (node (ref "MAX0") (pin "!DRDY") (pinfunction "~{DRDY}_!DRDY") (pintype "bidirectional"))
    )
    (net (code "87") (name "unconnected-(MAX0-~{FAULT}-Pad!FAULT)") (class "Default")
      (node (ref "MAX0") (pin "!FAULT") (pinfunction "~{FAULT}_!FAULT") (pintype "bidirectional"))
    )
    (net (code "88") (name "unconnected-(MAX1-DNC-Pad6)") (class "Default")
      (node (ref "MAX1") (pin "6") (pinfunction "DNC_6") (pintype "no_connect"))
    )
    (net (code "89") (name "unconnected-(MAX1-~{DRDY}-Pad!DRDY)") (class "Default")
      (node (ref "MAX1") (pin "!DRDY") (pinfunction "~{DRDY}_!DRDY") (pintype "bidirectional"))
    )
    (net (code "90") (name "unconnected-(MAX1-~{FAULT}-Pad!FAULT)") (class "Default")
      (node (ref "MAX1") (pin "!FAULT") (pinfunction "~{FAULT}_!FAULT") (pintype "bidirectional"))
    )
    (net (code "91") (name "unconnected-(MAX2-DNC-Pad6)") (class "Default")
      (node (ref "MAX2") (pin "6") (pinfunction "DNC_6") (pintype "no_connect"))
    )
    (net (code "92") (name "unconnected-(MAX2-~{DRDY}-Pad!DRDY)") (class "Default")
      (node (ref "MAX2") (pin "!DRDY") (pinfunction "~{DRDY}_!DRDY") (pintype "bidirectional"))
    )
    (net (code "93") (name "unconnected-(MAX2-~{FAULT}-Pad!FAULT)") (class "Default")
      (node (ref "MAX2") (pin "!FAULT") (pinfunction "~{FAULT}_!FAULT") (pintype "bidirectional"))
    )
    (net (code "94") (name "unconnected-(MAX3-DNC-Pad6)") (class "Default")
      (node (ref "MAX3") (pin "6") (pinfunction "DNC_6") (pintype "no_connect"))
    )
    (net (code "95") (name "unconnected-(MAX3-~{DRDY}-Pad!DRDY)") (class "Default")
      (node (ref "MAX3") (pin "!DRDY") (pinfunction "~{DRDY}_!DRDY") (pintype "bidirectional"))
    )
    (net (code "96") (name "unconnected-(MAX3-~{FAULT}-Pad!FAULT)") (class "Default")
      (node (ref "MAX3") (pin "!FAULT") (pinfunction "~{FAULT}_!FAULT") (pintype "bidirectional"))
    )
    (net (code "97") (name "unconnected-(MAX4-DNC-Pad6)") (class "Default")
      (node (ref "MAX4") (pin "6") (pinfunction "DNC_6") (pintype "no_connect"))
    )
    (net (code "98") (name "unconnected-(MAX4-~{DRDY}-Pad!DRDY)") (class "Default")
      (node (ref "MAX4") (pin "!DRDY") (pinfunction "~{DRDY}_!DRDY") (pintype "bidirectional"))
    )
    (net (code "99") (name "unconnected-(MAX4-~{FAULT}-Pad!FAULT)") (class "Default")
      (node (ref "MAX4") (pin "!FAULT") (pinfunction "~{FAULT}_!FAULT") (pintype "bidirectional"))
    )
    (net (code "100") (name "unconnected-(MAX5-DNC-Pad6)") (class "Default")
      (node (ref "MAX5") (pin "6") (pinfunction "DNC_6") (pintype "no_connect"))
    )
    (net (code "101") (name "unconnected-(MAX5-~{DRDY}-Pad!DRDY)") (class "Default")
      (node (ref "MAX5") (pin "!DRDY") (pinfunction "~{DRDY}_!DRDY") (pintype "bidirectional"))
    )
    (net (code "102") (name "unconnected-(MAX5-~{FAULT}-Pad!FAULT)") (class "Default")
      (node (ref "MAX5") (pin "!FAULT") (pinfunction "~{FAULT}_!FAULT") (pintype "bidirectional"))
    )
    (net (code "103") (name "unconnected-(MAX6-DNC-Pad6)") (class "Default")
      (node (ref "MAX6") (pin "6") (pinfunction "DNC_6") (pintype "no_connect"))
    )
    (net (code "104") (name "unconnected-(MAX6-~{DRDY}-Pad!DRDY)") (class "Default")
      (node (ref "MAX6") (pin "!DRDY") (pinfunction "~{DRDY}_!DRDY") (pintype "bidirectional"))
    )
    (net (code "105") (name "unconnected-(MAX6-~{FAULT}-Pad!FAULT)") (class "Default")
      (node (ref "MAX6") (pin "!FAULT") (pinfunction "~{FAULT}_!FAULT") (pintype "bidirectional"))
    )
    (net (code "106") (name "unconnected-(MAX7-DNC-Pad6)") (class "Default")
      (node (ref "MAX7") (pin "6") (pinfunction "DNC_6") (pintype "no_connect"))
    )
    (net (code "107") (name "unconnected-(MAX7-~{DRDY}-Pad!DRDY)") (class "Default")
      (node (ref "MAX7") (pin "!DRDY") (pinfunction "~{DRDY}_!DRDY") (pintype "bidirectional"))
    )
    (net (code "108") (name "unconnected-(MAX7-~{FAULT}-Pad!FAULT)") (class "Default")
      (node (ref "MAX7") (pin "!FAULT") (pinfunction "~{FAULT}_!FAULT") (pintype "bidirectional"))
    )
    (net (code "109") (name "unconnected-(RESET_BUTTON-PadP)") (class "Default")
      (node (ref "RESET_BUTTON") (pin "P") (pinfunction "P_P") (pintype "passive"))
    )
    (net (code "110") (name "unconnected-(RESET_BUTTON-PadS)") (class "Default")
      (node (ref "RESET_BUTTON") (pin "S") (pinfunction "S_S") (pintype "passive"))
    )
    (net (code "111") (name "unconnected-(TC0-PadP$3)") (class "Default")
      (node (ref "TC0") (pin "P$3") (pinfunction "P$3_P$3") (pintype "no_connect"))
    )
    (net (code "112") (name "unconnected-(TC0-PadP$4)") (class "Default")
      (node (ref "TC0") (pin "P$4") (pinfunction "P$4_P$4") (pintype "no_connect"))
    )
    (net (code "113") (name "unconnected-(TC1-PadP$3)") (class "Default")
      (node (ref "TC1") (pin "P$3") (pinfunction "P$3_P$3") (pintype "no_connect"))
    )
    (net (code "114") (name "unconnected-(TC1-PadP$4)") (class "Default")
      (node (ref "TC1") (pin "P$4") (pinfunction "P$4_P$4") (pintype "no_connect"))
    )
    (net (code "115") (name "unconnected-(TC2-PadP$3)") (class "Default")
      (node (ref "TC2") (pin "P$3") (pinfunction "P$3_P$3") (pintype "no_connect"))
    )
    (net (code "116") (name "unconnected-(TC2-PadP$4)") (class "Default")
      (node (ref "TC2") (pin "P$4") (pinfunction "P$4_P$4") (pintype "no_connect"))
    )
    (net (code "117") (name "unconnected-(TC3-PadP$3)") (class "Default")
      (node (ref "TC3") (pin "P$3") (pinfunction "P$3_P$3") (pintype "no_connect"))
    )
    (net (code "118") (name "unconnected-(TC3-PadP$4)") (class "Default")
      (node (ref "TC3") (pin "P$4") (pinfunction "P$4_P$4") (pintype "no_connect"))
    )
    (net (code "119") (name "unconnected-(TC4-PadP$3)") (class "Default")
      (node (ref "TC4") (pin "P$3") (pinfunction "P$3_P$3") (pintype "no_connect"))
    )
    (net (code "120") (name "unconnected-(TC4-PadP$4)") (class "Default")
      (node (ref "TC4") (pin "P$4") (pinfunction "P$4_P$4") (pintype "no_connect"))
    )
    (net (code "121") (name "unconnected-(TC5-PadP$3)") (class "Default")
      (node (ref "TC5") (pin "P$3") (pinfunction "P$3_P$3") (pintype "no_connect"))
    )
    (net (code "122") (name "unconnected-(TC5-PadP$4)") (class "Default")
      (node (ref "TC5") (pin "P$4") (pinfunction "P$4_P$4") (pintype "no_connect"))
    )
    (net (code "123") (name "unconnected-(TC6-PadP$3)") (class "Default")
      (node (ref "TC6") (pin "P$3") (pinfunction "P$3_P$3") (pintype "no_connect"))
    )
    (net (code "124") (name "unconnected-(TC6-PadP$4)") (class "Default")
      (node (ref "TC6") (pin "P$4") (pinfunction "P$4_P$4") (pintype "no_connect"))
    )
    (net (code "125") (name "unconnected-(TC7-PadP$3)") (class "Default")
      (node (ref "TC7") (pin "P$3") (pinfunction "P$3_P$3") (pintype "no_connect"))
    )
    (net (code "126") (name "unconnected-(TC7-PadP$4)") (class "Default")
      (node (ref "TC7") (pin "P$4") (pinfunction "P$4_P$4") (pintype "no_connect"))
    )
    (net (code "127") (name "unconnected-(U$2-GNDBREAK-PadP$3)") (class "Default")
      (node (ref "U$2") (pin "P$3") (pinfunction "GNDBREAK_P$3") (pintype "bidirectional"))
    )
    (net (code "128") (name "unconnected-(U$5-CARD_DETECT-PadCARD_DETECT1)") (class "Default")
      (node (ref "U$5") (pin "CARD_DETECT1") (pinfunction "CARD_DETECT_CARD_DETECT1") (pintype "passive"))
    )
    (net (code "129") (name "unconnected-(U$5-CARD_DETECT1-PadCARD_DETECT2)") (class "Default")
      (node (ref "U$5") (pin "CARD_DETECT2") (pinfunction "CARD_DETECT1_CARD_DETECT2") (pintype "passive"))
    )
    (net (code "130") (name "unconnected-(U1-ADC6-Pad19)") (class "Default")
      (node (ref "U1") (pin "19") (pinfunction "ADC6_19") (pintype "bidirectional"))
    )
    (net (code "131") (name "unconnected-(U1-ADC7-Pad22)") (class "Default")
      (node (ref "U1") (pin "22") (pinfunction "ADC7_22") (pintype "bidirectional"))
    )
    (net (code "132") (name "unconnected-(U1-AREF-Pad20)") (class "Default")
      (node (ref "U1") (pin "20") (pinfunction "AREF_20") (pintype "bidirectional"))
    )
    (net (code "133") (name "unconnected-(U1-PB7(XTAL2{slash}TOSC2)-Pad8)") (class "Default")
      (node (ref "U1") (pin "8") (pinfunction "PB7(XTAL2/TOSC2)_8") (pintype "bidirectional"))
    )
  )
)
